# Y1BVER2_0_4.net
KiCad netlist of a schematic drawn in Altium Designer
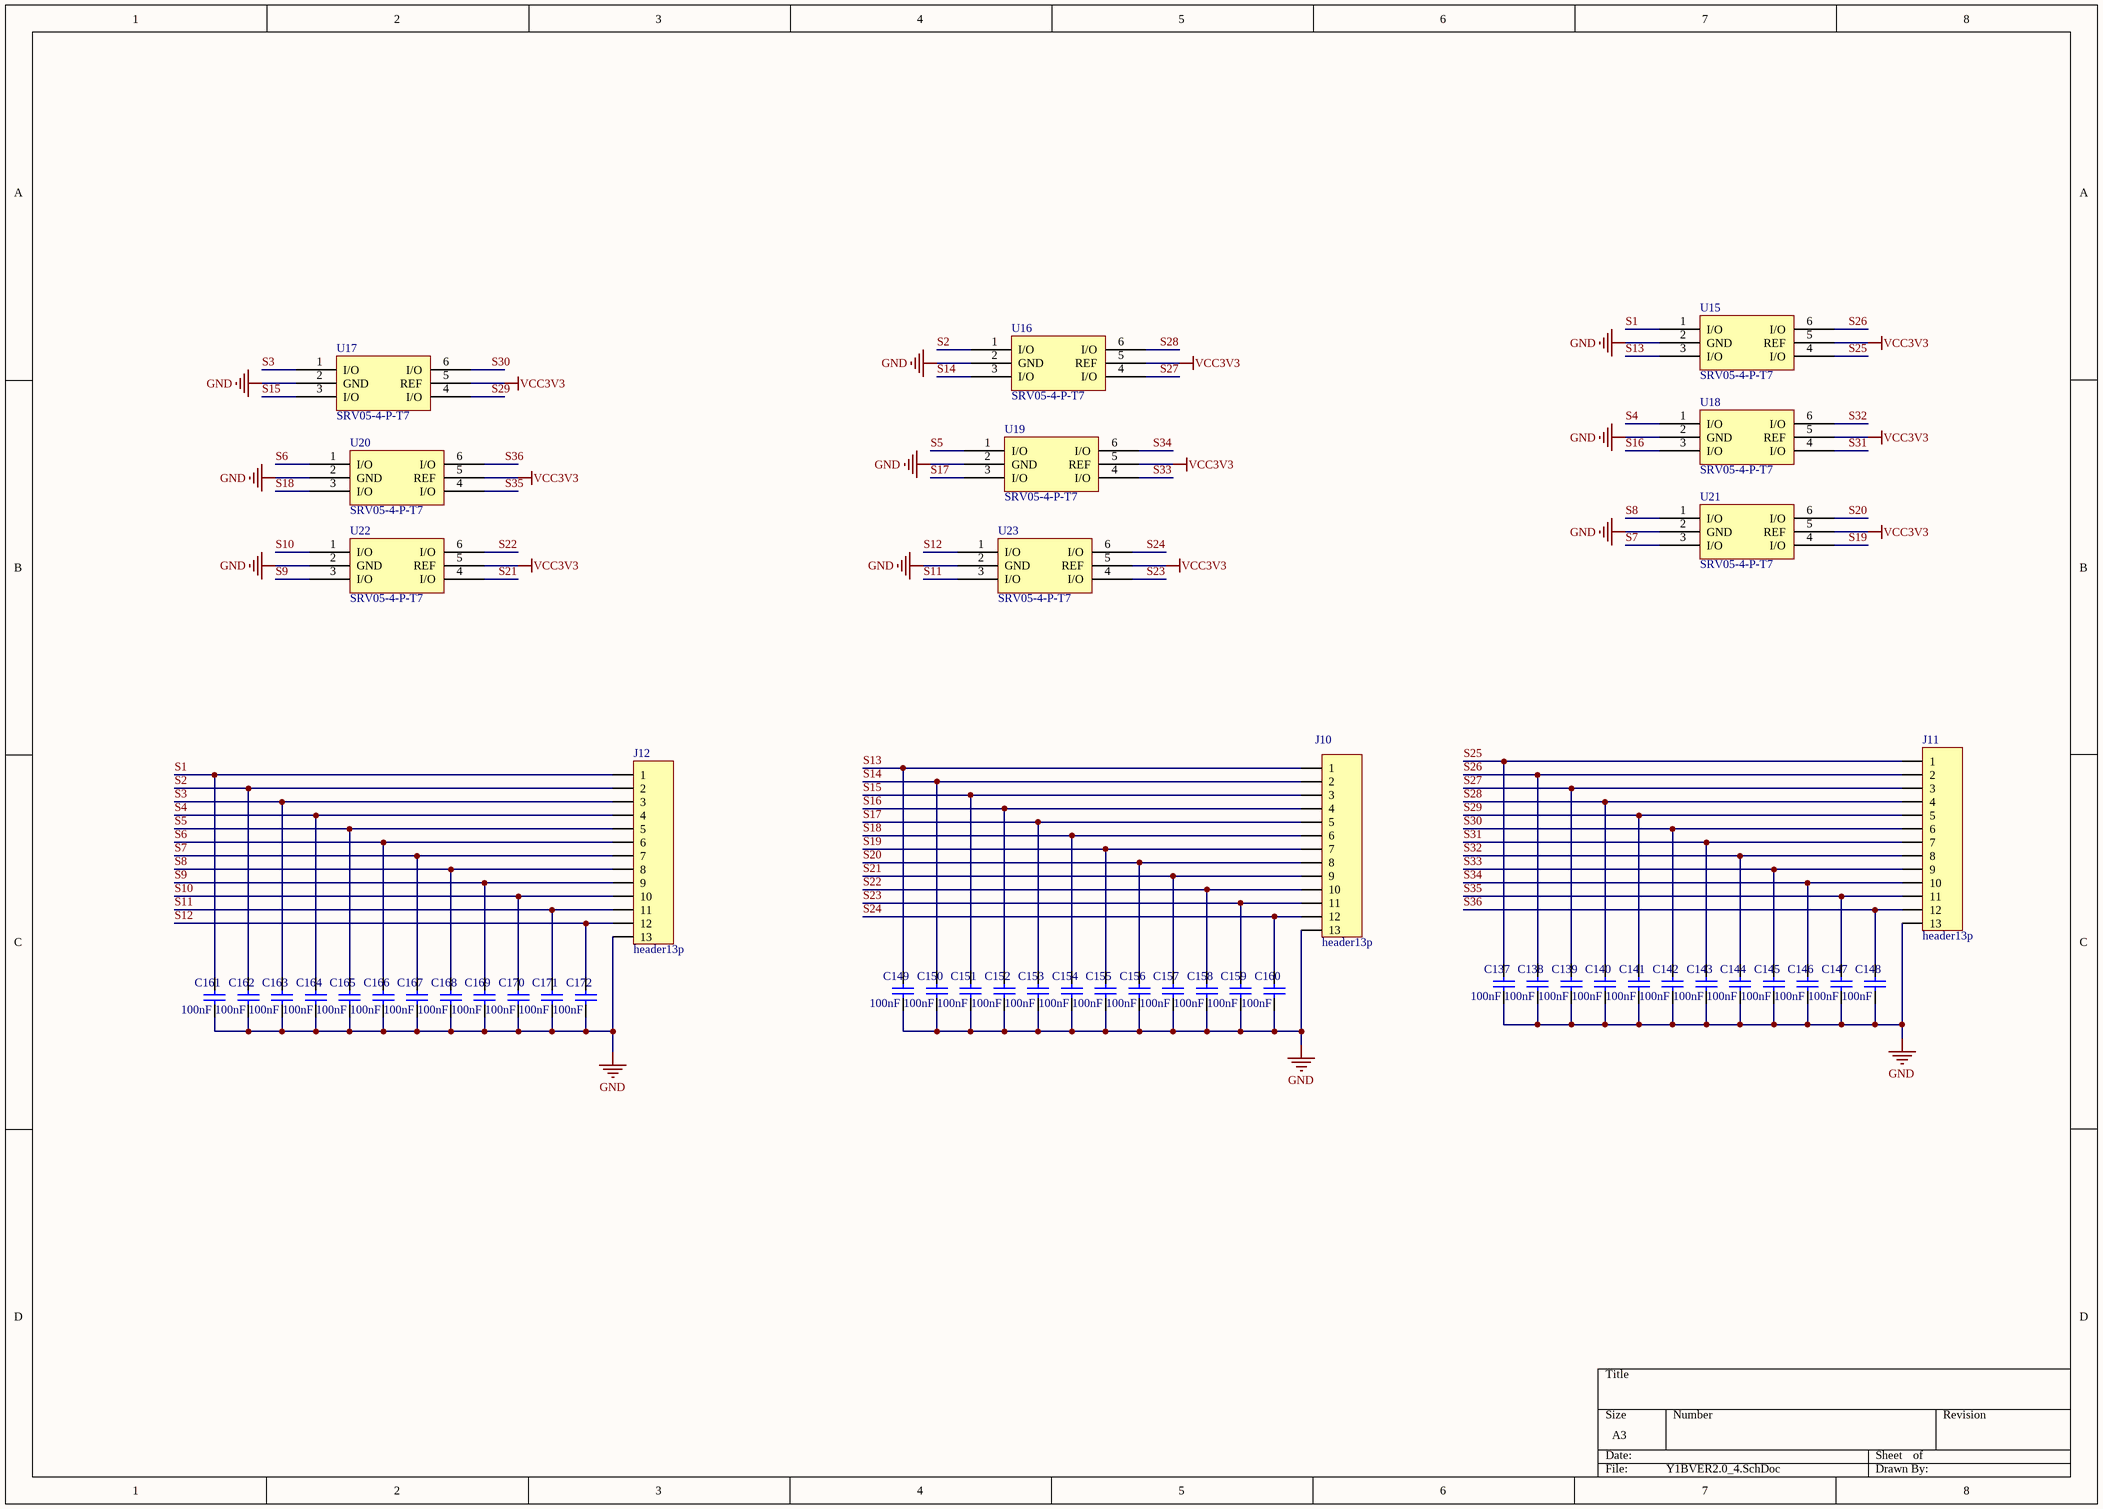
[diagram p0: Y1BVER2.0_4.SchDoc]

(export (version "E")
  (design (tool "Eeschema 10.0.6"))
  (components
    (comp (ref "C137")
      (value "100nF")
      (footprint "0603_C")
      (description "贴片电容")
      (libsource (lib "AD封装2018.9.19Miscellaneous Devices LC") (part "0603 100nF (104) 10% 50V"))
    )
    (comp (ref "C138")
      (value "100nF")
      (footprint "0603_C")
      (description "贴片电容")
      (libsource (lib "AD封装2018.9.19Miscellaneous Devices LC") (part "0603 100nF (104) 10% 50V"))
    )
    (comp (ref "C139")
      (value "100nF")
      (footprint "0603_C")
      (description "贴片电容")
      (libsource (lib "AD封装2018.9.19Miscellaneous Devices LC") (part "0603 100nF (104) 10% 50V"))
    )
    (comp (ref "C140")
      (value "100nF")
      (footprint "0603_C")
      (description "贴片电容")
      (libsource (lib "AD封装2018.9.19Miscellaneous Devices LC") (part "0603 100nF (104) 10% 50V"))
    )
    (comp (ref "C141")
      (value "100nF")
      (footprint "0603_C")
      (description "贴片电容")
      (libsource (lib "AD封装2018.9.19Miscellaneous Devices LC") (part "0603 100nF (104) 10% 50V"))
    )
    (comp (ref "C142")
      (value "100nF")
      (footprint "0603_C")
      (description "贴片电容")
      (libsource (lib "AD封装2018.9.19Miscellaneous Devices LC") (part "0603 100nF (104) 10% 50V"))
    )
    (comp (ref "C143")
      (value "100nF")
      (footprint "0603_C")
      (description "贴片电容")
      (libsource (lib "AD封装2018.9.19Miscellaneous Devices LC") (part "0603 100nF (104) 10% 50V"))
    )
    (comp (ref "C144")
      (value "100nF")
      (footprint "0603_C")
      (description "贴片电容")
      (libsource (lib "AD封装2018.9.19Miscellaneous Devices LC") (part "0603 100nF (104) 10% 50V"))
    )
    (comp (ref "C145")
      (value "100nF")
      (footprint "0603_C")
      (description "贴片电容")
      (libsource (lib "AD封装2018.9.19Miscellaneous Devices LC") (part "0603 100nF (104) 10% 50V"))
    )
    (comp (ref "C146")
      (value "100nF")
      (footprint "0603_C")
      (description "贴片电容")
      (libsource (lib "AD封装2018.9.19Miscellaneous Devices LC") (part "0603 100nF (104) 10% 50V"))
    )
    (comp (ref "C147")
      (value "100nF")
      (footprint "0603_C")
      (description "贴片电容")
      (libsource (lib "AD封装2018.9.19Miscellaneous Devices LC") (part "0603 100nF (104) 10% 50V"))
    )
    (comp (ref "C148")
      (value "100nF")
      (footprint "0603_C")
      (description "贴片电容")
      (libsource (lib "AD封装2018.9.19Miscellaneous Devices LC") (part "0603 100nF (104) 10% 50V"))
    )
    (comp (ref "C149")
      (value "100nF")
      (footprint "0603_C")
      (description "贴片电容")
      (libsource (lib "AD封装2018.9.19Miscellaneous Devices LC") (part "0603 100nF (104) 10% 50V"))
    )
    (comp (ref "C150")
      (value "100nF")
      (footprint "0603_C")
      (description "贴片电容")
      (libsource (lib "AD封装2018.9.19Miscellaneous Devices LC") (part "0603 100nF (104) 10% 50V"))
    )
    (comp (ref "C151")
      (value "100nF")
      (footprint "0603_C")
      (description "贴片电容")
      (libsource (lib "AD封装2018.9.19Miscellaneous Devices LC") (part "0603 100nF (104) 10% 50V"))
    )
    (comp (ref "C152")
      (value "100nF")
      (footprint "0603_C")
      (description "贴片电容")
      (libsource (lib "AD封装2018.9.19Miscellaneous Devices LC") (part "0603 100nF (104) 10% 50V"))
    )
    (comp (ref "C153")
      (value "100nF")
      (footprint "0603_C")
      (description "贴片电容")
      (libsource (lib "AD封装2018.9.19Miscellaneous Devices LC") (part "0603 100nF (104) 10% 50V"))
    )
    (comp (ref "C154")
      (value "100nF")
      (footprint "0603_C")
      (description "贴片电容")
      (libsource (lib "AD封装2018.9.19Miscellaneous Devices LC") (part "0603 100nF (104) 10% 50V"))
    )
    (comp (ref "C155")
      (value "100nF")
      (footprint "0603_C")
      (description "贴片电容")
      (libsource (lib "AD封装2018.9.19Miscellaneous Devices LC") (part "0603 100nF (104) 10% 50V"))
    )
    (comp (ref "C156")
      (value "100nF")
      (footprint "0603_C")
      (description "贴片电容")
      (libsource (lib "AD封装2018.9.19Miscellaneous Devices LC") (part "0603 100nF (104) 10% 50V"))
    )
    (comp (ref "C157")
      (value "100nF")
      (footprint "0603_C")
      (description "贴片电容")
      (libsource (lib "AD封装2018.9.19Miscellaneous Devices LC") (part "0603 100nF (104) 10% 50V"))
    )
    (comp (ref "C158")
      (value "100nF")
      (footprint "0603_C")
      (description "贴片电容")
      (libsource (lib "AD封装2018.9.19Miscellaneous Devices LC") (part "0603 100nF (104) 10% 50V"))
    )
    (comp (ref "C159")
      (value "100nF")
      (footprint "0603_C")
      (description "贴片电容")
      (libsource (lib "AD封装2018.9.19Miscellaneous Devices LC") (part "0603 100nF (104) 10% 50V"))
    )
    (comp (ref "C160")
      (value "100nF")
      (footprint "0603_C")
      (description "贴片电容")
      (libsource (lib "AD封装2018.9.19Miscellaneous Devices LC") (part "0603 100nF (104) 10% 50V"))
    )
    (comp (ref "C161")
      (value "100nF")
      (footprint "0603_C")
      (description "贴片电容")
      (libsource (lib "AD封装2018.9.19Miscellaneous Devices LC") (part "0603 100nF (104) 10% 50V"))
    )
    (comp (ref "C162")
      (value "100nF")
      (footprint "0603_C")
      (description "贴片电容")
      (libsource (lib "AD封装2018.9.19Miscellaneous Devices LC") (part "0603 100nF (104) 10% 50V"))
    )
    (comp (ref "C163")
      (value "100nF")
      (footprint "0603_C")
      (description "贴片电容")
      (libsource (lib "AD封装2018.9.19Miscellaneous Devices LC") (part "0603 100nF (104) 10% 50V"))
    )
    (comp (ref "C164")
      (value "100nF")
      (footprint "0603_C")
      (description "贴片电容")
      (libsource (lib "AD封装2018.9.19Miscellaneous Devices LC") (part "0603 100nF (104) 10% 50V"))
    )
    (comp (ref "C165")
      (value "100nF")
      (footprint "0603_C")
      (description "贴片电容")
      (libsource (lib "AD封装2018.9.19Miscellaneous Devices LC") (part "0603 100nF (104) 10% 50V"))
    )
    (comp (ref "C166")
      (value "100nF")
      (footprint "0603_C")
      (description "贴片电容")
      (libsource (lib "AD封装2018.9.19Miscellaneous Devices LC") (part "0603 100nF (104) 10% 50V"))
    )
    (comp (ref "C167")
      (value "100nF")
      (footprint "0603_C")
      (description "贴片电容")
      (libsource (lib "AD封装2018.9.19Miscellaneous Devices LC") (part "0603 100nF (104) 10% 50V"))
    )
    (comp (ref "C168")
      (value "100nF")
      (footprint "0603_C")
      (description "贴片电容")
      (libsource (lib "AD封装2018.9.19Miscellaneous Devices LC") (part "0603 100nF (104) 10% 50V"))
    )
    (comp (ref "C169")
      (value "100nF")
      (footprint "0603_C")
      (description "贴片电容")
      (libsource (lib "AD封装2018.9.19Miscellaneous Devices LC") (part "0603 100nF (104) 10% 50V"))
    )
    (comp (ref "C170")
      (value "100nF")
      (footprint "0603_C")
      (description "贴片电容")
      (libsource (lib "AD封装2018.9.19Miscellaneous Devices LC") (part "0603 100nF (104) 10% 50V"))
    )
    (comp (ref "C171")
      (value "100nF")
      (footprint "0603_C")
      (description "贴片电容")
      (libsource (lib "AD封装2018.9.19Miscellaneous Devices LC") (part "0603 100nF (104) 10% 50V"))
    )
    (comp (ref "C172")
      (value "100nF")
      (footprint "0603_C")
      (description "贴片电容")
      (libsource (lib "AD封装2018.9.19Miscellaneous Devices LC") (part "0603 100nF (104) 10% 50V"))
    )
    (comp (ref "J10") (value "header13p") (footprint "xh-13") (libsource (lib "我的集成库") (part "header13p")))
    (comp (ref "J11") (value "header13p") (footprint "xh-13") (libsource (lib "我的集成库") (part "header13p")))
    (comp (ref "J12") (value "header13p") (footprint "xh-13") (libsource (lib "我的集成库") (part "header13p")))
    (comp (ref "U15")
      (value "SRV05-4-P-T7")
      (footprint "SOT-23-6")
      (description "TVS")
      (libsource (lib "AD封装2018.9.19Miscellaneous Devices LC") (part "SRV05-4-P-T7_[C85364]"))
    )
    (comp (ref "U16")
      (value "SRV05-4-P-T7")
      (footprint "SOT-23-6")
      (description "TVS")
      (libsource (lib "AD封装2018.9.19Miscellaneous Devices LC") (part "SRV05-4-P-T7_[C85364]"))
    )
    (comp (ref "U17")
      (value "SRV05-4-P-T7")
      (footprint "SOT-23-6")
      (description "TVS")
      (libsource (lib "AD封装2018.9.19Miscellaneous Devices LC") (part "SRV05-4-P-T7_[C85364]"))
    )
    (comp (ref "U18")
      (value "SRV05-4-P-T7")
      (footprint "SOT-23-6")
      (description "TVS")
      (libsource (lib "AD封装2018.9.19Miscellaneous Devices LC") (part "SRV05-4-P-T7_[C85364]"))
    )
    (comp (ref "U19")
      (value "SRV05-4-P-T7")
      (footprint "SOT-23-6")
      (description "TVS")
      (libsource (lib "AD封装2018.9.19Miscellaneous Devices LC") (part "SRV05-4-P-T7_[C85364]"))
    )
    (comp (ref "U20")
      (value "SRV05-4-P-T7")
      (footprint "SOT-23-6")
      (description "TVS")
      (libsource (lib "AD封装2018.9.19Miscellaneous Devices LC") (part "SRV05-4-P-T7_[C85364]"))
    )
    (comp (ref "U21")
      (value "SRV05-4-P-T7")
      (footprint "SOT-23-6")
      (description "TVS")
      (libsource (lib "AD封装2018.9.19Miscellaneous Devices LC") (part "SRV05-4-P-T7_[C85364]"))
    )
    (comp (ref "U22")
      (value "SRV05-4-P-T7")
      (footprint "SOT-23-6")
      (description "TVS")
      (libsource (lib "AD封装2018.9.19Miscellaneous Devices LC") (part "SRV05-4-P-T7_[C85364]"))
    )
    (comp (ref "U23")
      (value "SRV05-4-P-T7")
      (footprint "SOT-23-6")
      (description "TVS")
      (libsource (lib "AD封装2018.9.19Miscellaneous Devices LC") (part "SRV05-4-P-T7_[C85364]"))
    )
  )
  (nets
    (net (code "1") (name "/S1") (class "Default")
      (node (ref "C161") (pin "1") (pinfunction "1_1") (pintype "passive"))
      (node (ref "J12") (pin "1") (pinfunction "1_1") (pintype "passive"))
      (node (ref "U15") (pin "1") (pinfunction "I/O_1") (pintype "passive"))
    )
    (net (code "2") (name "/S2") (class "Default")
      (node (ref "C162") (pin "1") (pinfunction "1_1") (pintype "passive"))
      (node (ref "J12") (pin "2") (pinfunction "2_2") (pintype "passive"))
      (node (ref "U16") (pin "1") (pinfunction "I/O_1") (pintype "passive"))
    )
    (net (code "3") (name "/S3") (class "Default")
      (node (ref "C163") (pin "1") (pinfunction "1_1") (pintype "passive"))
      (node (ref "J12") (pin "3") (pinfunction "3_3") (pintype "passive"))
      (node (ref "U17") (pin "1") (pinfunction "I/O_1") (pintype "passive"))
    )
    (net (code "4") (name "/S4") (class "Default")
      (node (ref "C164") (pin "1") (pinfunction "1_1") (pintype "passive"))
      (node (ref "J12") (pin "4") (pinfunction "4_4") (pintype "passive"))
      (node (ref "U18") (pin "1") (pinfunction "I/O_1") (pintype "passive"))
    )
    (net (code "5") (name "/S5") (class "Default")
      (node (ref "C165") (pin "1") (pinfunction "1_1") (pintype "passive"))
      (node (ref "J12") (pin "5") (pinfunction "5_5") (pintype "passive"))
      (node (ref "U19") (pin "1") (pinfunction "I/O_1") (pintype "passive"))
    )
    (net (code "6") (name "/S6") (class "Default")
      (node (ref "C166") (pin "1") (pinfunction "1_1") (pintype "passive"))
      (node (ref "J12") (pin "6") (pinfunction "6_6") (pintype "passive"))
      (node (ref "U20") (pin "1") (pinfunction "I/O_1") (pintype "passive"))
    )
    (net (code "7") (name "/S7") (class "Default")
      (node (ref "C167") (pin "1") (pinfunction "1_1") (pintype "passive"))
      (node (ref "J12") (pin "7") (pinfunction "7_7") (pintype "passive"))
      (node (ref "U21") (pin "3") (pinfunction "I/O_3") (pintype "passive"))
    )
    (net (code "8") (name "/S8") (class "Default")
      (node (ref "C168") (pin "1") (pinfunction "1_1") (pintype "passive"))
      (node (ref "J12") (pin "8") (pinfunction "8_8") (pintype "passive"))
      (node (ref "U21") (pin "1") (pinfunction "I/O_1") (pintype "passive"))
    )
    (net (code "9") (name "/S9") (class "Default")
      (node (ref "C169") (pin "1") (pinfunction "1_1") (pintype "passive"))
      (node (ref "J12") (pin "9") (pinfunction "9_9") (pintype "passive"))
      (node (ref "U22") (pin "3") (pinfunction "I/O_3") (pintype "passive"))
    )
    (net (code "10") (name "/S10") (class "Default")
      (node (ref "C170") (pin "1") (pinfunction "1_1") (pintype "passive"))
      (node (ref "J12") (pin "10") (pinfunction "10_10") (pintype "passive"))
      (node (ref "U22") (pin "1") (pinfunction "I/O_1") (pintype "passive"))
    )
    (net (code "11") (name "/S11") (class "Default")
      (node (ref "C171") (pin "1") (pinfunction "1_1") (pintype "passive"))
      (node (ref "J12") (pin "11") (pinfunction "11_11") (pintype "passive"))
      (node (ref "U23") (pin "3") (pinfunction "I/O_3") (pintype "passive"))
    )
    (net (code "12") (name "/S12") (class "Default")
      (node (ref "C172") (pin "1") (pinfunction "1_1") (pintype "passive"))
      (node (ref "J12") (pin "12") (pinfunction "12_12") (pintype "passive"))
      (node (ref "U23") (pin "1") (pinfunction "I/O_1") (pintype "passive"))
    )
    (net (code "13") (name "/S13") (class "Default")
      (node (ref "C149") (pin "1") (pinfunction "1_1") (pintype "passive"))
      (node (ref "J10") (pin "1") (pinfunction "1_1") (pintype "passive"))
      (node (ref "U15") (pin "3") (pinfunction "I/O_3") (pintype "passive"))
    )
    (net (code "14") (name "/S14") (class "Default")
      (node (ref "C150") (pin "1") (pinfunction "1_1") (pintype "passive"))
      (node (ref "J10") (pin "2") (pinfunction "2_2") (pintype "passive"))
      (node (ref "U16") (pin "3") (pinfunction "I/O_3") (pintype "passive"))
    )
    (net (code "15") (name "/S15") (class "Default")
      (node (ref "C151") (pin "1") (pinfunction "1_1") (pintype "passive"))
      (node (ref "J10") (pin "3") (pinfunction "3_3") (pintype "passive"))
      (node (ref "U17") (pin "3") (pinfunction "I/O_3") (pintype "passive"))
    )
    (net (code "16") (name "/S16") (class "Default")
      (node (ref "C152") (pin "1") (pinfunction "1_1") (pintype "passive"))
      (node (ref "J10") (pin "4") (pinfunction "4_4") (pintype "passive"))
      (node (ref "U18") (pin "3") (pinfunction "I/O_3") (pintype "passive"))
    )
    (net (code "17") (name "/S17") (class "Default")
      (node (ref "C153") (pin "1") (pinfunction "1_1") (pintype "passive"))
      (node (ref "J10") (pin "5") (pinfunction "5_5") (pintype "passive"))
      (node (ref "U19") (pin "3") (pinfunction "I/O_3") (pintype "passive"))
    )
    (net (code "18") (name "/S18") (class "Default")
      (node (ref "C154") (pin "1") (pinfunction "1_1") (pintype "passive"))
      (node (ref "J10") (pin "6") (pinfunction "6_6") (pintype "passive"))
      (node (ref "U20") (pin "3") (pinfunction "I/O_3") (pintype "passive"))
    )
    (net (code "19") (name "/S19") (class "Default")
      (node (ref "C155") (pin "1") (pinfunction "1_1") (pintype "passive"))
      (node (ref "J10") (pin "7") (pinfunction "7_7") (pintype "passive"))
      (node (ref "U21") (pin "4") (pinfunction "I/O_4") (pintype "passive"))
    )
    (net (code "20") (name "/S20") (class "Default")
      (node (ref "C156") (pin "1") (pinfunction "1_1") (pintype "passive"))
      (node (ref "J10") (pin "8") (pinfunction "8_8") (pintype "passive"))
      (node (ref "U21") (pin "6") (pinfunction "I/O_6") (pintype "passive"))
    )
    (net (code "21") (name "/S21") (class "Default")
      (node (ref "C157") (pin "1") (pinfunction "1_1") (pintype "passive"))
      (node (ref "J10") (pin "9") (pinfunction "9_9") (pintype "passive"))
      (node (ref "U22") (pin "4") (pinfunction "I/O_4") (pintype "passive"))
    )
    (net (code "22") (name "/S22") (class "Default")
      (node (ref "C158") (pin "1") (pinfunction "1_1") (pintype "passive"))
      (node (ref "J10") (pin "10") (pinfunction "10_10") (pintype "passive"))
      (node (ref "U22") (pin "6") (pinfunction "I/O_6") (pintype "passive"))
    )
    (net (code "23") (name "/S23") (class "Default")
      (node (ref "C159") (pin "1") (pinfunction "1_1") (pintype "passive"))
      (node (ref "J10") (pin "11") (pinfunction "11_11") (pintype "passive"))
      (node (ref "U23") (pin "4") (pinfunction "I/O_4") (pintype "passive"))
    )
    (net (code "24") (name "/S24") (class "Default")
      (node (ref "C160") (pin "1") (pinfunction "1_1") (pintype "passive"))
      (node (ref "J10") (pin "12") (pinfunction "12_12") (pintype "passive"))
      (node (ref "U23") (pin "6") (pinfunction "I/O_6") (pintype "passive"))
    )
    (net (code "25") (name "/S25") (class "Default")
      (node (ref "C137") (pin "1") (pinfunction "1_1") (pintype "passive"))
      (node (ref "J11") (pin "1") (pinfunction "1_1") (pintype "passive"))
      (node (ref "U15") (pin "4") (pinfunction "I/O_4") (pintype "passive"))
    )
    (net (code "26") (name "/S26") (class "Default")
      (node (ref "C138") (pin "1") (pinfunction "1_1") (pintype "passive"))
      (node (ref "J11") (pin "2") (pinfunction "2_2") (pintype "passive"))
      (node (ref "U15") (pin "6") (pinfunction "I/O_6") (pintype "passive"))
    )
    (net (code "27") (name "/S27") (class "Default")
      (node (ref "C139") (pin "1") (pinfunction "1_1") (pintype "passive"))
      (node (ref "J11") (pin "3") (pinfunction "3_3") (pintype "passive"))
      (node (ref "U16") (pin "4") (pinfunction "I/O_4") (pintype "passive"))
    )
    (net (code "28") (name "/S28") (class "Default")
      (node (ref "C140") (pin "1") (pinfunction "1_1") (pintype "passive"))
      (node (ref "J11") (pin "4") (pinfunction "4_4") (pintype "passive"))
      (node (ref "U16") (pin "6") (pinfunction "I/O_6") (pintype "passive"))
    )
    (net (code "29") (name "/S29") (class "Default")
      (node (ref "C141") (pin "1") (pinfunction "1_1") (pintype "passive"))
      (node (ref "J11") (pin "5") (pinfunction "5_5") (pintype "passive"))
      (node (ref "U17") (pin "4") (pinfunction "I/O_4") (pintype "passive"))
    )
    (net (code "30") (name "/S30") (class "Default")
      (node (ref "C142") (pin "1") (pinfunction "1_1") (pintype "passive"))
      (node (ref "J11") (pin "6") (pinfunction "6_6") (pintype "passive"))
      (node (ref "U17") (pin "6") (pinfunction "I/O_6") (pintype "passive"))
    )
    (net (code "31") (name "/S31") (class "Default")
      (node (ref "C143") (pin "1") (pinfunction "1_1") (pintype "passive"))
      (node (ref "J11") (pin "7") (pinfunction "7_7") (pintype "passive"))
      (node (ref "U18") (pin "4") (pinfunction "I/O_4") (pintype "passive"))
    )
    (net (code "32") (name "/S32") (class "Default")
      (node (ref "C144") (pin "1") (pinfunction "1_1") (pintype "passive"))
      (node (ref "J11") (pin "8") (pinfunction "8_8") (pintype "passive"))
      (node (ref "U18") (pin "6") (pinfunction "I/O_6") (pintype "passive"))
    )
    (net (code "33") (name "/S33") (class "Default")
      (node (ref "C145") (pin "1") (pinfunction "1_1") (pintype "passive"))
      (node (ref "J11") (pin "9") (pinfunction "9_9") (pintype "passive"))
      (node (ref "U19") (pin "4") (pinfunction "I/O_4") (pintype "passive"))
    )
    (net (code "34") (name "/S34") (class "Default")
      (node (ref "C146") (pin "1") (pinfunction "1_1") (pintype "passive"))
      (node (ref "J11") (pin "10") (pinfunction "10_10") (pintype "passive"))
      (node (ref "U19") (pin "6") (pinfunction "I/O_6") (pintype "passive"))
    )
    (net (code "35") (name "/S35") (class "Default")
      (node (ref "C147") (pin "1") (pinfunction "1_1") (pintype "passive"))
      (node (ref "J11") (pin "11") (pinfunction "11_11") (pintype "passive"))
      (node (ref "U20") (pin "4") (pinfunction "I/O_4") (pintype "passive"))
    )
    (net (code "36") (name "/S36") (class "Default")
      (node (ref "C148") (pin "1") (pinfunction "1_1") (pintype "passive"))
      (node (ref "J11") (pin "12") (pinfunction "12_12") (pintype "passive"))
      (node (ref "U20") (pin "6") (pinfunction "I/O_6") (pintype "passive"))
    )
    (net (code "37") (name "GND") (class "Default")
      (node (ref "C137") (pin "2") (pinfunction "2_2") (pintype "passive"))
      (node (ref "C138") (pin "2") (pinfunction "2_2") (pintype "passive"))
      (node (ref "C139") (pin "2") (pinfunction "2_2") (pintype "passive"))
      (node (ref "C140") (pin "2") (pinfunction "2_2") (pintype "passive"))
      (node (ref "C141") (pin "2") (pinfunction "2_2") (pintype "passive"))
      (node (ref "C142") (pin "2") (pinfunction "2_2") (pintype "passive"))
      (node (ref "C143") (pin "2") (pinfunction "2_2") (pintype "passive"))
      (node (ref "C144") (pin "2") (pinfunction "2_2") (pintype "passive"))
      (node (ref "C145") (pin "2") (pinfunction "2_2") (pintype "passive"))
      (node (ref "C146") (pin "2") (pinfunction "2_2") (pintype "passive"))
      (node (ref "C147") (pin "2") (pinfunction "2_2") (pintype "passive"))
      (node (ref "C148") (pin "2") (pinfunction "2_2") (pintype "passive"))
      (node (ref "C149") (pin "2") (pinfunction "2_2") (pintype "passive"))
      (node (ref "C150") (pin "2") (pinfunction "2_2") (pintype "passive"))
      (node (ref "C151") (pin "2") (pinfunction "2_2") (pintype "passive"))
      (node (ref "C152") (pin "2") (pinfunction "2_2") (pintype "passive"))
      (node (ref "C153") (pin "2") (pinfunction "2_2") (pintype "passive"))
      (node (ref "C154") (pin "2") (pinfunction "2_2") (pintype "passive"))
      (node (ref "C155") (pin "2") (pinfunction "2_2") (pintype "passive"))
      (node (ref "C156") (pin "2") (pinfunction "2_2") (pintype "passive"))
      (node (ref "C157") (pin "2") (pinfunction "2_2") (pintype "passive"))
      (node (ref "C158") (pin "2") (pinfunction "2_2") (pintype "passive"))
      (node (ref "C159") (pin "2") (pinfunction "2_2") (pintype "passive"))
      (node (ref "C160") (pin "2") (pinfunction "2_2") (pintype "passive"))
      (node (ref "C161") (pin "2") (pinfunction "2_2") (pintype "passive"))
      (node (ref "C162") (pin "2") (pinfunction "2_2") (pintype "passive"))
      (node (ref "C163") (pin "2") (pinfunction "2_2") (pintype "passive"))
      (node (ref "C164") (pin "2") (pinfunction "2_2") (pintype "passive"))
      (node (ref "C165") (pin "2") (pinfunction "2_2") (pintype "passive"))
      (node (ref "C166") (pin "2") (pinfunction "2_2") (pintype "passive"))
      (node (ref "C167") (pin "2") (pinfunction "2_2") (pintype "passive"))
      (node (ref "C168") (pin "2") (pinfunction "2_2") (pintype "passive"))
      (node (ref "C169") (pin "2") (pinfunction "2_2") (pintype "passive"))
      (node (ref "C170") (pin "2") (pinfunction "2_2") (pintype "passive"))
      (node (ref "C171") (pin "2") (pinfunction "2_2") (pintype "passive"))
      (node (ref "C172") (pin "2") (pinfunction "2_2") (pintype "passive"))
      (node (ref "J10") (pin "13") (pinfunction "13_13") (pintype "passive"))
      (node (ref "J11") (pin "13") (pinfunction "13_13") (pintype "passive"))
      (node (ref "J12") (pin "13") (pinfunction "13_13") (pintype "passive"))
      (node (ref "U15") (pin "2") (pinfunction "GND_2") (pintype "passive"))
      (node (ref "U16") (pin "2") (pinfunction "GND_2") (pintype "passive"))
      (node (ref "U17") (pin "2") (pinfunction "GND_2") (pintype "passive"))
      (node (ref "U18") (pin "2") (pinfunction "GND_2") (pintype "passive"))
      (node (ref "U19") (pin "2") (pinfunction "GND_2") (pintype "passive"))
      (node (ref "U20") (pin "2") (pinfunction "GND_2") (pintype "passive"))
      (node (ref "U21") (pin "2") (pinfunction "GND_2") (pintype "passive"))
      (node (ref "U22") (pin "2") (pinfunction "GND_2") (pintype "passive"))
      (node (ref "U23") (pin "2") (pinfunction "GND_2") (pintype "passive"))
    )
    (net (code "38") (name "VCC3V3") (class "Default")
      (node (ref "U15") (pin "5") (pinfunction "REF_5") (pintype "passive"))
      (node (ref "U16") (pin "5") (pinfunction "REF_5") (pintype "passive"))
      (node (ref "U17") (pin "5") (pinfunction "REF_5") (pintype "passive"))
      (node (ref "U18") (pin "5") (pinfunction "REF_5") (pintype "passive"))
      (node (ref "U19") (pin "5") (pinfunction "REF_5") (pintype "passive"))
      (node (ref "U20") (pin "5") (pinfunction "REF_5") (pintype "passive"))
      (node (ref "U21") (pin "5") (pinfunction "REF_5") (pintype "passive"))
      (node (ref "U22") (pin "5") (pinfunction "REF_5") (pintype "passive"))
      (node (ref "U23") (pin "5") (pinfunction "REF_5") (pintype "passive"))
    )
  )
)
